# POW_MCU.net
KiCad netlist of a schematic drawn in Altium Designer
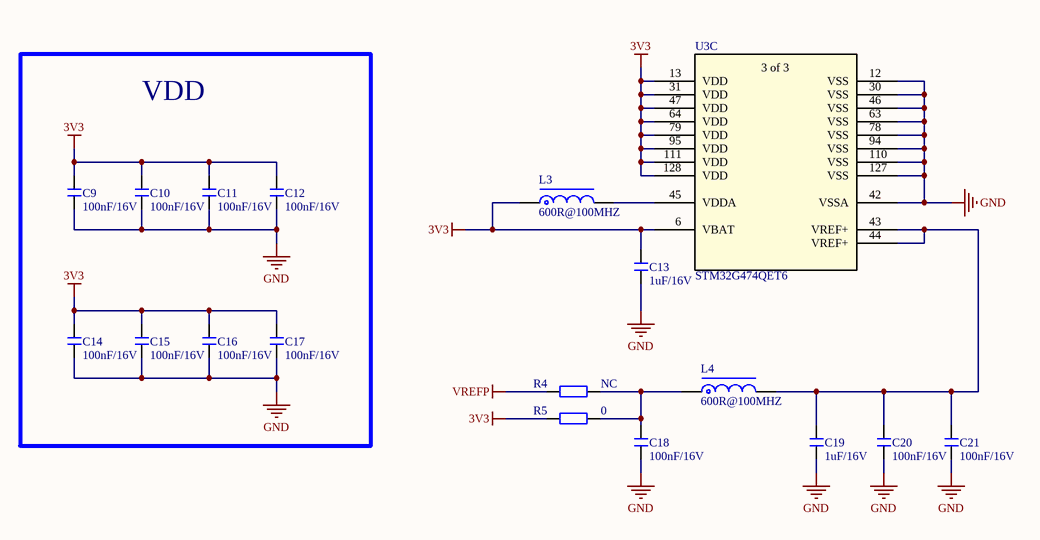
[diagram p0: POW_MCU.SchDoc]

(export (version "E")
  (design (tool "Eeschema 10.0.6"))
  (components
    (comp (ref "C9")
      (value "100nF/16V")
      (footprint "C 0402_L")
      (description "贴片电容")
      (libsource (lib "3.1   - 电阻-电容-电感") (part "C"))
    )
    (comp (ref "C10")
      (value "100nF/16V")
      (footprint "C 0402_L")
      (description "贴片电容")
      (libsource (lib "3.1   - 电阻-电容-电感") (part "C"))
    )
    (comp (ref "C11")
      (value "100nF/16V")
      (footprint "C 0402_L")
      (description "贴片电容")
      (libsource (lib "3.1   - 电阻-电容-电感") (part "C"))
    )
    (comp (ref "C12")
      (value "100nF/16V")
      (footprint "C 0402_L")
      (description "贴片电容")
      (libsource (lib "3.1   - 电阻-电容-电感") (part "C"))
    )
    (comp (ref "C13")
      (value "1uF/16V")
      (footprint "C 0402_L")
      (description "贴片电容")
      (libsource (lib "3.1   - 电阻-电容-电感") (part "C"))
    )
    (comp (ref "C14")
      (value "100nF/16V")
      (footprint "C 0402_L")
      (description "贴片电容")
      (libsource (lib "3.1   - 电阻-电容-电感") (part "C"))
    )
    (comp (ref "C15")
      (value "100nF/16V")
      (footprint "C 0402_L")
      (description "贴片电容")
      (libsource (lib "3.1   - 电阻-电容-电感") (part "C"))
    )
    (comp (ref "C16")
      (value "100nF/16V")
      (footprint "C 0402_L")
      (description "贴片电容")
      (libsource (lib "3.1   - 电阻-电容-电感") (part "C"))
    )
    (comp (ref "C17")
      (value "100nF/16V")
      (footprint "C 0402_L")
      (description "贴片电容")
      (libsource (lib "3.1   - 电阻-电容-电感") (part "C"))
    )
    (comp (ref "C18")
      (value "100nF/16V")
      (footprint "C 0402_L")
      (description "贴片电容")
      (libsource (lib "3.1   - 电阻-电容-电感") (part "C"))
    )
    (comp (ref "C19")
      (value "1uF/16V")
      (footprint "C 0402_L")
      (description "贴片电容")
      (libsource (lib "3.1   - 电阻-电容-电感") (part "C"))
    )
    (comp (ref "C20")
      (value "100nF/16V")
      (footprint "C 0402_L")
      (description "贴片电容")
      (libsource (lib "3.1   - 电阻-电容-电感") (part "C"))
    )
    (comp (ref "C21")
      (value "100nF/16V")
      (footprint "C 0402_L")
      (description "贴片电容")
      (libsource (lib "3.1   - 电阻-电容-电感") (part "C"))
    )
    (comp (ref "L3")
      (value "600R@100MHZ")
      (footprint "L 0603")
      (description "XFL4020-222MEB")
      (libsource (lib "3.1   - 电阻-电容-电感") (part "L-CD"))
    )
    (comp (ref "L4")
      (value "600R@100MHZ")
      (footprint "L 0603")
      (description "XFL4020-222MEB")
      (libsource (lib "3.1   - 电阻-电容-电感") (part "L-CD"))
    )
    (comp (ref "R4")
      (value "NC")
      (footprint "R 0402_L")
      (description "贴片电阻")
      (libsource (lib "3.1   - 电阻-电容-电感") (part "R"))
    )
    (comp (ref "R5")
      (value "0")
      (footprint "R 0402_L")
      (description "贴片电阻")
      (libsource (lib "3.1   - 电阻-电容-电感") (part "R"))
    )
    (comp (ref "U3")
      (value "STM32G474QET6")
      (footprint "LQFP128 14x14_L")
      (description "No Description Available")
      (fields (field (name "COPYRIGHT") "Copyright (C) 2018 Accelerated Designs. All rights reserved"))
      (libsource (lib "2021-04-22_13-53-57") (part "STM32G474QET6"))
    )
  )
  (nets
    (net (code "1") (name "3V3") (class "Default")
      (node (ref "C10") (pin "2") (pinfunction "2_2") (pintype "passive"))
      (node (ref "C11") (pin "2") (pinfunction "2_2") (pintype "passive"))
      (node (ref "C12") (pin "2") (pinfunction "2_2") (pintype "passive"))
      (node (ref "C13") (pin "1") (pinfunction "1_1") (pintype "passive"))
      (node (ref "C14") (pin "2") (pinfunction "2_2") (pintype "passive"))
      (node (ref "C15") (pin "2") (pinfunction "2_2") (pintype "passive"))
      (node (ref "C16") (pin "2") (pinfunction "2_2") (pintype "passive"))
      (node (ref "C17") (pin "2") (pinfunction "2_2") (pintype "passive"))
      (node (ref "C9") (pin "2") (pinfunction "2_2") (pintype "passive"))
      (node (ref "L3") (pin "1") (pinfunction "1_1") (pintype "passive"))
      (node (ref "R5") (pin "1") (pinfunction "1_1") (pintype "passive"))
      (node (ref "U3") (pin "111") (pinfunction "VDD_111") (pintype "power_in"))
      (node (ref "U3") (pin "128") (pinfunction "VDD_128") (pintype "power_in"))
      (node (ref "U3") (pin "13") (pinfunction "VDD_13") (pintype "power_in"))
      (node (ref "U3") (pin "31") (pinfunction "VDD_31") (pintype "power_in"))
      (node (ref "U3") (pin "47") (pinfunction "VDD_47") (pintype "power_in"))
      (node (ref "U3") (pin "6") (pinfunction "VBAT_6") (pintype "power_in"))
      (node (ref "U3") (pin "64") (pinfunction "VDD_64") (pintype "power_in"))
      (node (ref "U3") (pin "79") (pinfunction "VDD_79") (pintype "power_in"))
      (node (ref "U3") (pin "95") (pinfunction "VDD_95") (pintype "power_in"))
    )
    (net (code "2") (name "GND") (class "Default")
      (node (ref "C10") (pin "1") (pinfunction "1_1") (pintype "passive"))
      (node (ref "C11") (pin "1") (pinfunction "1_1") (pintype "passive"))
      (node (ref "C12") (pin "1") (pinfunction "1_1") (pintype "passive"))
      (node (ref "C13") (pin "2") (pinfunction "2_2") (pintype "passive"))
      (node (ref "C14") (pin "1") (pinfunction "1_1") (pintype "passive"))
      (node (ref "C15") (pin "1") (pinfunction "1_1") (pintype "passive"))
      (node (ref "C16") (pin "1") (pinfunction "1_1") (pintype "passive"))
      (node (ref "C17") (pin "1") (pinfunction "1_1") (pintype "passive"))
      (node (ref "C18") (pin "1") (pinfunction "1_1") (pintype "passive"))
      (node (ref "C19") (pin "2") (pinfunction "2_2") (pintype "passive"))
      (node (ref "C20") (pin "1") (pinfunction "1_1") (pintype "passive"))
      (node (ref "C21") (pin "1") (pinfunction "1_1") (pintype "passive"))
      (node (ref "C9") (pin "1") (pinfunction "1_1") (pintype "passive"))
      (node (ref "U3") (pin "110") (pinfunction "VSS_110") (pintype "power_in"))
      (node (ref "U3") (pin "12") (pinfunction "VSS_12") (pintype "power_in"))
      (node (ref "U3") (pin "127") (pinfunction "VSS_127") (pintype "power_in"))
      (node (ref "U3") (pin "30") (pinfunction "VSS_30") (pintype "power_in"))
      (node (ref "U3") (pin "42") (pinfunction "VSSA_42") (pintype "power_in"))
      (node (ref "U3") (pin "46") (pinfunction "VSS_46") (pintype "power_in"))
      (node (ref "U3") (pin "63") (pinfunction "VSS_63") (pintype "power_in"))
      (node (ref "U3") (pin "78") (pinfunction "VSS_78") (pintype "power_in"))
      (node (ref "U3") (pin "94") (pinfunction "VSS_94") (pintype "power_in"))
    )
    (net (code "3") (name "Net-(C18-Pad2)") (class "Default")
      (node (ref "C18") (pin "2") (pinfunction "2_2") (pintype "passive"))
      (node (ref "L4") (pin "1") (pinfunction "1_1") (pintype "passive"))
      (node (ref "R4") (pin "2") (pinfunction "2_2") (pintype "passive"))
      (node (ref "R5") (pin "2") (pinfunction "2_2") (pintype "passive"))
    )
    (net (code "4") (name "Net-(C19-Pad1)") (class "Default")
      (node (ref "C19") (pin "1") (pinfunction "1_1") (pintype "passive"))
      (node (ref "C20") (pin "2") (pinfunction "2_2") (pintype "passive"))
      (node (ref "C21") (pin "2") (pinfunction "2_2") (pintype "passive"))
      (node (ref "L4") (pin "2") (pinfunction "2_2") (pintype "passive"))
      (node (ref "U3") (pin "43") (pinfunction "VREF+_43") (pintype "power_in"))
      (node (ref "U3") (pin "44") (pinfunction "VREF+_44") (pintype "power_in"))
    )
    (net (code "5") (name "Net-(U3C-VDDA)") (class "Default")
      (node (ref "L3") (pin "2") (pinfunction "2_2") (pintype "passive"))
      (node (ref "U3") (pin "45") (pinfunction "VDDA_45") (pintype "power_in"))
    )
    (net (code "6") (name "VREFP") (class "Default")
      (node (ref "R4") (pin "1") (pinfunction "1_1") (pintype "passive"))
    )
  )
)
